# Qwiic_Pocket_Dev_ESP32_C6.net
KiCad netlist of a schematic drawn in EAGLE
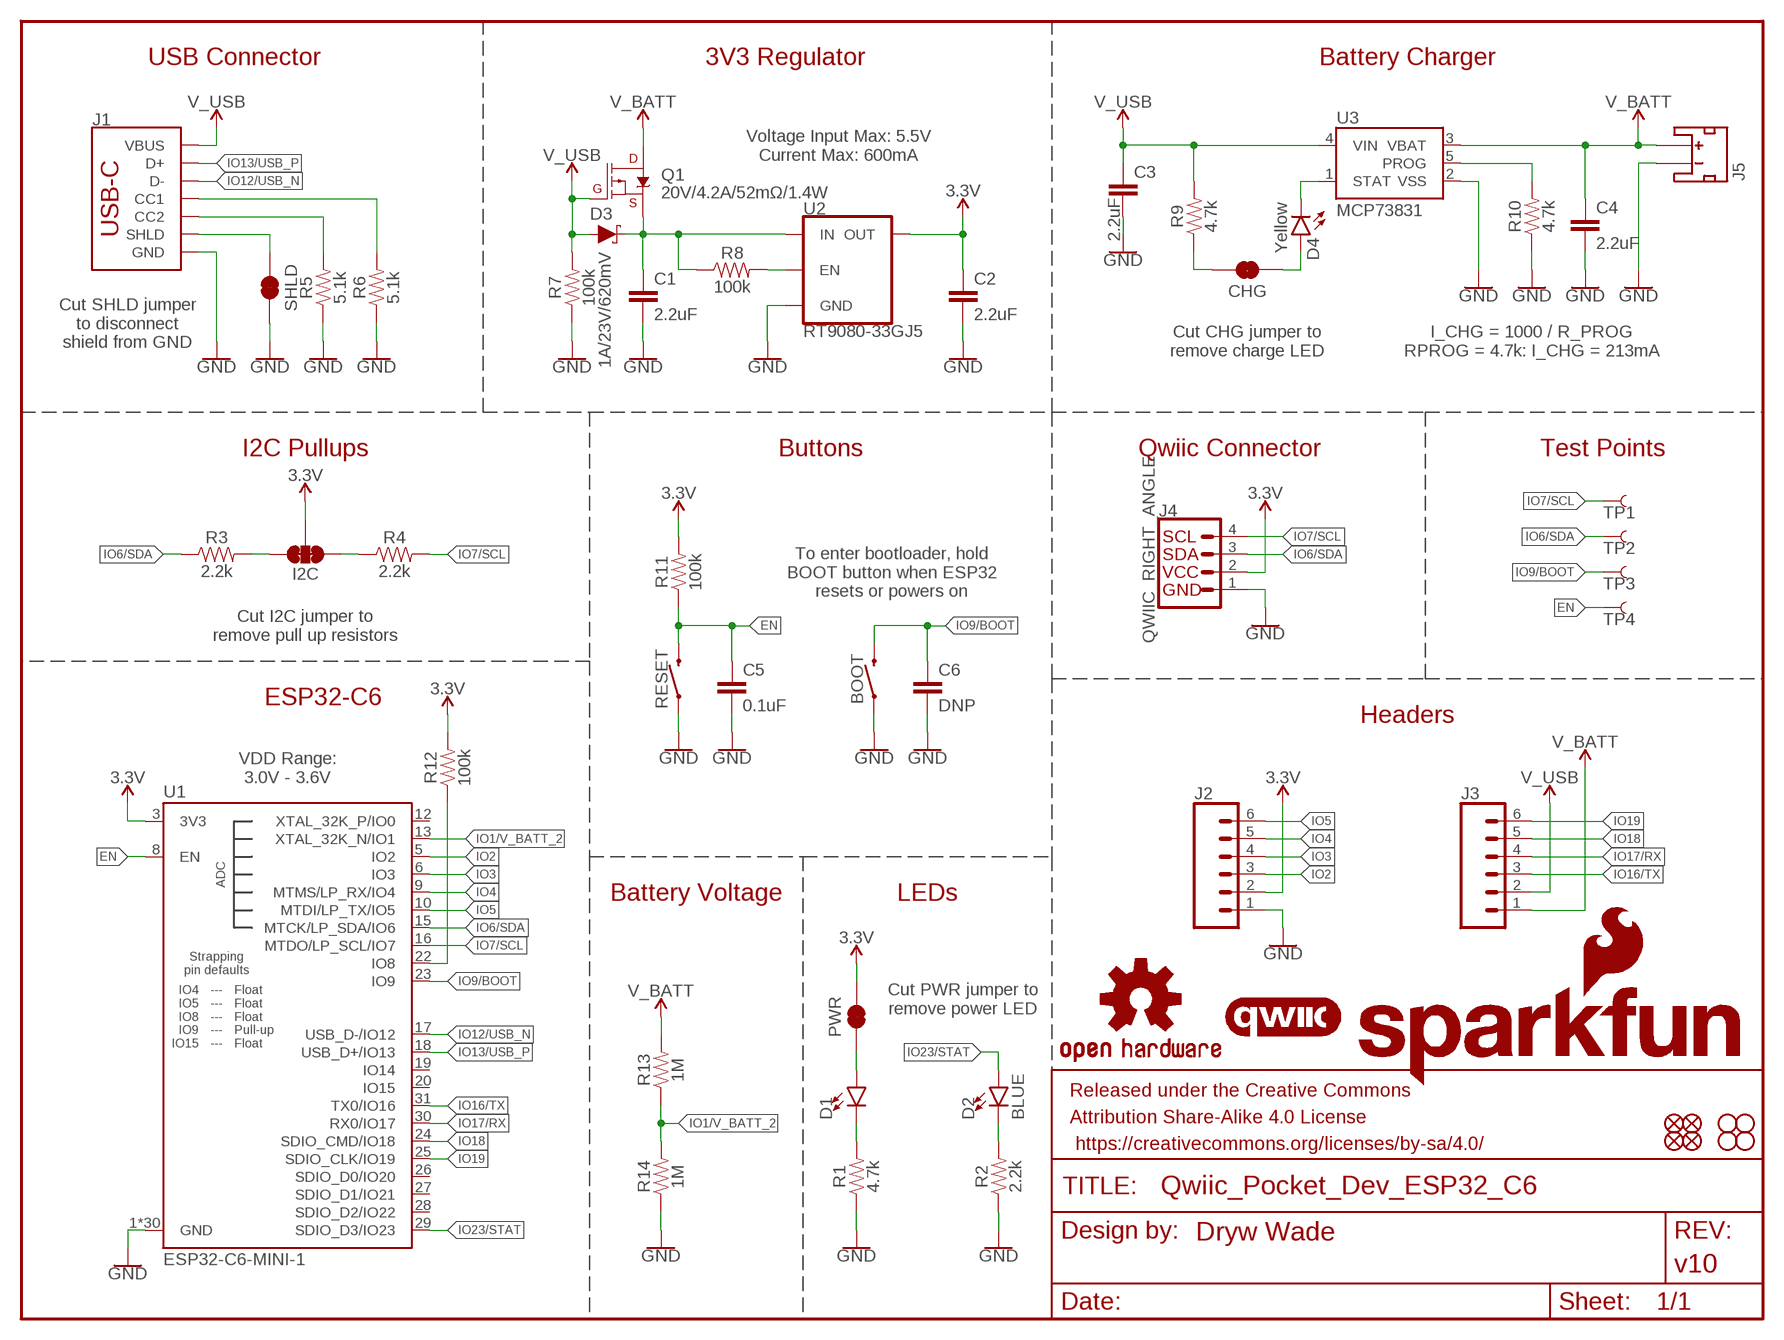
[diagram p0: schematic, sheet 1]

(export (version "E")
  (design (tool "Eeschema 10.0.6"))
  (components
    (comp (ref "BOOT")
      (value "MOMENTARY-SWITCH-SPST-SMD-4.6X2.8MM")
      (footprint "eagle-import:TACTILE_SWITCH_SMD_4.6X2.8MM")
      (libsource (lib "eagle-import") (part "MOMENTARY-SWITCH-SPST-SMD-4.6X2.8MM"))
    )
    (comp (ref "C1")
      (value "2.2uF")
      (footprint "eagle-import:0402-TIGHT")
      (libsource (lib "eagle-import") (part "2.2UF-0402_TIGHT-10V-10%-X5R"))
    )
    (comp (ref "C2")
      (value "2.2uF")
      (footprint "eagle-import:0402-TIGHT")
      (libsource (lib "eagle-import") (part "2.2UF-0402_TIGHT-10V-10%-X5R"))
    )
    (comp (ref "C3")
      (value "2.2uF")
      (footprint "eagle-import:0402-TIGHT")
      (libsource (lib "eagle-import") (part "2.2UF-0402_TIGHT-10V-10%-X5R"))
    )
    (comp (ref "C4")
      (value "2.2uF")
      (footprint "eagle-import:0402-TIGHT")
      (libsource (lib "eagle-import") (part "2.2UF-0402_TIGHT-10V-10%-X5R"))
    )
    (comp (ref "C5")
      (value "0.1uF")
      (footprint "eagle-import:0402-TIGHT")
      (libsource (lib "eagle-import") (part "0.1UF-0402T-6.3V-10%-X7R"))
    )
    (comp (ref "C6")
      (value "DNP")
      (footprint "eagle-import:0402-TIGHT")
      (libsource (lib "eagle-import") (part "0.1UF-0402T-6.3V-10%-X7R"))
    )
    (comp (ref "CHG")
      (value "JUMPER-SMT_2_NC_TRACE_SILK")
      (footprint "eagle-import:SMT-JUMPER_2_NC_TRACE_SILK")
      (libsource (lib "eagle-import") (part "JUMPER-SMT_2_NC_TRACE_SILK"))
    )
    (comp (ref "D1")
      (value "LED-RED_0603-KB")
      (footprint "eagle-import:LED-0603")
      (libsource (lib "eagle-import") (part "LED-RED_0603-KB"))
    )
    (comp (ref "D2")
      (value "BLUE")
      (footprint "eagle-import:LED-0603")
      (libsource (lib "eagle-import") (part "LED-BLUE0603"))
    )
    (comp (ref "D3")
      (value "1A/23V/620mV")
      (footprint "eagle-import:SOD-323")
      (libsource (lib "eagle-import") (part "DIODE-SCHOTTKY-BAT20J"))
    )
    (comp (ref "D4")
      (value "Yellow")
      (footprint "eagle-import:LED-0603")
      (libsource (lib "eagle-import") (part "LED-YELLOW0603"))
    )
    (comp (ref "FD1")
      (value "FIDUCIALUFIDUCIAL")
      (footprint "eagle-import:FIDUCIAL-MICRO")
      (libsource (lib "eagle-import") (part "FIDUCIALUFIDUCIAL"))
    )
    (comp (ref "FD2")
      (value "FIDUCIALUFIDUCIAL")
      (footprint "eagle-import:FIDUCIAL-MICRO")
      (libsource (lib "eagle-import") (part "FIDUCIALUFIDUCIAL"))
    )
    (comp (ref "FD3")
      (value "FIDUCIALUFIDUCIAL")
      (footprint "eagle-import:FIDUCIAL-MICRO")
      (libsource (lib "eagle-import") (part "FIDUCIALUFIDUCIAL"))
    )
    (comp (ref "FD4")
      (value "FIDUCIALUFIDUCIAL")
      (footprint "eagle-import:FIDUCIAL-MICRO")
      (libsource (lib "eagle-import") (part "FIDUCIALUFIDUCIAL"))
    )
    (comp (ref "FRAME1")
      (value "FRAME-LETTER")
      (footprint "eagle-import:CREATIVE_COMMONS")
      (fields (field (name "DESIGNER") "Dryw Wade") (field (name "REV") "v10"))
      (libsource (lib "eagle-import") (part "FRAME-LETTER"))
    )
    (comp (ref "H1")
      (value "STAND-OFF")
      (footprint "eagle-import:STAND-OFF")
      (libsource (lib "eagle-import") (part "STAND-OFF"))
    )
    (comp (ref "H2")
      (value "STAND-OFF")
      (footprint "eagle-import:STAND-OFF")
      (libsource (lib "eagle-import") (part "STAND-OFF"))
    )
    (comp (ref "H3")
      (value "STAND-OFF")
      (footprint "eagle-import:STAND-OFF")
      (libsource (lib "eagle-import") (part "STAND-OFF"))
    )
    (comp (ref "H4")
      (value "STAND-OFF")
      (footprint "eagle-import:STAND-OFF")
      (libsource (lib "eagle-import") (part "STAND-OFF"))
    )
    (comp (ref "I2C")
      (value "JUMPER-SMT_3_2-NC_TRACE_SILK")
      (footprint "eagle-import:SMT-JUMPER_3_2-NC_TRACE_SILK")
      (libsource (lib "eagle-import") (part "JUMPER-SMT_3_2-NC_TRACE_SILK"))
    )
    (comp (ref "J1")
      (value "USB Female Type C Connector")
      (footprint "eagle-import:USB-C-16P_4LAYER-PADS")
      (libsource (lib "eagle-import") (part "USB_C_4-LAYER_PADS"))
    )
    (comp (ref "J2")
      (value "CONN_06NO_SILK_NO_POP")
      (footprint "eagle-import:1X06_NO_SILK")
      (libsource (lib "eagle-import") (part "CONN_06NO_SILK_NO_POP"))
    )
    (comp (ref "J3")
      (value "CONN_06NO_SILK_NO_POP")
      (footprint "eagle-import:1X06_NO_SILK")
      (libsource (lib "eagle-import") (part "CONN_06NO_SILK_NO_POP"))
    )
    (comp (ref "J4")
      (value "QWIIC_RIGHT_ANGLE")
      (footprint "eagle-import:JST04_1MM_RA")
      (libsource (lib "eagle-import") (part "QWIIC_CONNECTORJS-1MM"))
    )
    (comp (ref "J5")
      (value "JST_2MM_MALE")
      (footprint "eagle-import:JST-2-SMD")
      (libsource (lib "eagle-import") (part "JST_2MM_MALE"))
    )
    (comp (ref "LOGO1")
      (value "SFE_LOGO_NAME_FLAMEBLANK")
      (footprint "eagle-import:BLANK")
      (libsource (lib "eagle-import") (part "SFE_LOGO_NAME_FLAMEBLANK"))
    )
    (comp (ref "LOGO2")
      (value "OSHW-LOGOS")
      (footprint "eagle-import:OSHW-LOGO-S")
      (libsource (lib "eagle-import") (part "OSHW-LOGOS"))
    )
    (comp (ref "LOGO3")
      (value "QWIIC_LOGO_3MM")
      (footprint "eagle-import:QWIIC_3MM")
      (libsource (lib "eagle-import") (part "QWIIC_LOGO_3MM"))
    )
    (comp (ref "PWR")
      (value "JUMPER-SMT_2_NC_TRACE_SILK")
      (footprint "eagle-import:SMT-JUMPER_2_NC_TRACE_SILK")
      (libsource (lib "eagle-import") (part "JUMPER-SMT_2_NC_TRACE_SILK"))
    )
    (comp (ref "Q1")
      (value "20V/4.2A/52mΩ/1.4W")
      (footprint "eagle-import:SOT23-3")
      (libsource (lib "eagle-import") (part "MOSFET_PCH-DMG2305UX-7"))
    )
    (comp (ref "R1")
      (value "4.7k")
      (footprint "eagle-import:0402-TIGHT")
      (libsource (lib "eagle-import") (part "4.7KOHM-0402T-1/16W-1%"))
    )
    (comp (ref "R2")
      (value "2.2k")
      (footprint "eagle-import:0402-TIGHT")
      (libsource (lib "eagle-import") (part "2.2KOHM-0402T-1/16W-1%"))
    )
    (comp (ref "R3")
      (value "2.2k")
      (footprint "eagle-import:0402-TIGHT")
      (libsource (lib "eagle-import") (part "2.2KOHM-0402T-1/16W-1%"))
    )
    (comp (ref "R4")
      (value "2.2k")
      (footprint "eagle-import:0402-TIGHT")
      (libsource (lib "eagle-import") (part "2.2KOHM-0402T-1/16W-1%"))
    )
    (comp (ref "R5")
      (value "5.1k")
      (footprint "eagle-import:0402-TIGHT")
      (libsource (lib "eagle-import") (part "5.1KOHM-0402T-1/16W-1%"))
    )
    (comp (ref "R6")
      (value "5.1k")
      (footprint "eagle-import:0402-TIGHT")
      (libsource (lib "eagle-import") (part "5.1KOHM-0402T-1/16W-1%"))
    )
    (comp (ref "R7")
      (value "100k")
      (footprint "eagle-import:0402-TIGHT")
      (libsource (lib "eagle-import") (part "100KOHM-0402T-1/16W-1%"))
    )
    (comp (ref "R8")
      (value "100k")
      (footprint "eagle-import:0402-TIGHT")
      (libsource (lib "eagle-import") (part "100KOHM-0402T-1/16W-1%"))
    )
    (comp (ref "R9")
      (value "4.7k")
      (footprint "eagle-import:0402-TIGHT")
      (libsource (lib "eagle-import") (part "4.7KOHM-0402T-1/16W-1%"))
    )
    (comp (ref "R10")
      (value "4.7k")
      (footprint "eagle-import:0402-TIGHT")
      (libsource (lib "eagle-import") (part "4.7KOHM-0402T-1/16W-1%"))
    )
    (comp (ref "R11")
      (value "100k")
      (footprint "eagle-import:0402-TIGHT")
      (libsource (lib "eagle-import") (part "100KOHM-0402T-1/16W-1%"))
    )
    (comp (ref "R12")
      (value "100k")
      (footprint "eagle-import:0402-TIGHT")
      (libsource (lib "eagle-import") (part "100KOHM-0402T-1/16W-1%"))
    )
    (comp (ref "R13")
      (value "1M")
      (footprint "eagle-import:0402-TIGHT")
      (libsource (lib "eagle-import") (part "1MOHM-0402T-1/16W-5%"))
    )
    (comp (ref "R14")
      (value "1M")
      (footprint "eagle-import:0402-TIGHT")
      (libsource (lib "eagle-import") (part "1MOHM-0402T-1/16W-5%"))
    )
    (comp (ref "RESET")
      (value "MOMENTARY-SWITCH-SPST-SMD-4.6X2.8MM")
      (footprint "eagle-import:TACTILE_SWITCH_SMD_4.6X2.8MM")
      (libsource (lib "eagle-import") (part "MOMENTARY-SWITCH-SPST-SMD-4.6X2.8MM"))
    )
    (comp (ref "SHLD")
      (value "JUMPER-SMT_2_NC_TRACE_SILK")
      (footprint "eagle-import:SMT-JUMPER_2_NC_TRACE_SILK")
      (libsource (lib "eagle-import") (part "JUMPER-SMT_2_NC_TRACE_SILK"))
    )
    (comp (ref "TP1")
      (value "TEST-POINT3")
      (footprint "eagle-import:PAD.03X.03")
      (libsource (lib "eagle-import") (part "TEST-POINT3"))
    )
    (comp (ref "TP2")
      (value "TEST-POINT3")
      (footprint "eagle-import:PAD.03X.03")
      (libsource (lib "eagle-import") (part "TEST-POINT3"))
    )
    (comp (ref "TP3")
      (value "TEST-POINT3")
      (footprint "eagle-import:PAD.03X.03")
      (libsource (lib "eagle-import") (part "TEST-POINT3"))
    )
    (comp (ref "TP4")
      (value "TEST-POINT3")
      (footprint "eagle-import:PAD.03X.03")
      (libsource (lib "eagle-import") (part "TEST-POINT3"))
    )
    (comp (ref "U1")
      (value "ESP32-C6-MINI-1")
      (footprint "eagle-import:ESP32-C6-MINI-1")
      (libsource (lib "eagle-import") (part "ESP32-C6-MINI-1"))
    )
    (comp (ref "U2")
      (value "RT9080-33GJ5")
      (footprint "eagle-import:SOT23-5")
      (libsource (lib "eagle-import") (part "V_REG_RT9080"))
    )
    (comp (ref "U3")
      (value "MCP73831")
      (footprint "eagle-import:SOT23-5")
      (libsource (lib "eagle-import") (part "MCP73831"))
    )
  )
  (nets
    (net (code "1") (name "3.3V") (class "Default")
      (node (ref "C2") (pin "1") (pinfunction "1_1") (pintype "passive"))
      (node (ref "I2C") (pin "2") (pinfunction "2_2") (pintype "passive"))
      (node (ref "J2") (pin "2") (pinfunction "2_2") (pintype "passive"))
      (node (ref "J4") (pin "2") (pinfunction "2_2") (pintype "power_in"))
      (node (ref "PWR") (pin "2") (pinfunction "2_2") (pintype "passive"))
      (node (ref "R11") (pin "2") (pinfunction "2_2") (pintype "passive"))
      (node (ref "R12") (pin "2") (pinfunction "2_2") (pintype "passive"))
      (node (ref "U1") (pin "3") (pinfunction "3V3_3") (pintype "bidirectional"))
      (node (ref "U2") (pin "5") (pinfunction "OUT_5") (pintype "passive"))
    )
    (net (code "2") (name "EN") (class "Default")
      (node (ref "C5") (pin "1") (pinfunction "1_1") (pintype "passive"))
      (node (ref "R11") (pin "1") (pinfunction "1_1") (pintype "passive"))
      (node (ref "RESET") (pin "3") (pinfunction "2_3") (pintype "passive"))
      (node (ref "RESET") (pin "4") (pinfunction "2_4") (pintype "passive"))
      (node (ref "TP4") (pin "1") (pinfunction "1_1") (pintype "bidirectional"))
      (node (ref "U1") (pin "8") (pinfunction "EN_8") (pintype "bidirectional"))
    )
    (net (code "3") (name "GND") (class "Default")
      (node (ref "BOOT") (pin "1") (pinfunction "1_1") (pintype "passive"))
      (node (ref "BOOT") (pin "2") (pinfunction "1_2") (pintype "passive"))
      (node (ref "C1") (pin "2") (pinfunction "2_2") (pintype "passive"))
      (node (ref "C2") (pin "2") (pinfunction "2_2") (pintype "passive"))
      (node (ref "C3") (pin "2") (pinfunction "2_2") (pintype "passive"))
      (node (ref "C4") (pin "2") (pinfunction "2_2") (pintype "passive"))
      (node (ref "C5") (pin "2") (pinfunction "2_2") (pintype "passive"))
      (node (ref "C6") (pin "2") (pinfunction "2_2") (pintype "passive"))
      (node (ref "J1") (pin "GND") (pinfunction "GND_GND") (pintype "bidirectional"))
      (node (ref "J1") (pin "GND2") (pinfunction "GND_GND2") (pintype "bidirectional"))
      (node (ref "J2") (pin "1") (pinfunction "1_1") (pintype "passive"))
      (node (ref "J4") (pin "1") (pinfunction "1_1") (pintype "power_in"))
      (node (ref "J5") (pin "1") (pinfunction "-_1") (pintype "bidirectional"))
      (node (ref "R1") (pin "1") (pinfunction "1_1") (pintype "passive"))
      (node (ref "R10") (pin "1") (pinfunction "1_1") (pintype "passive"))
      (node (ref "R14") (pin "1") (pinfunction "1_1") (pintype "passive"))
      (node (ref "R2") (pin "1") (pinfunction "1_1") (pintype "passive"))
      (node (ref "R5") (pin "1") (pinfunction "1_1") (pintype "passive"))
      (node (ref "R6") (pin "1") (pinfunction "1_1") (pintype "passive"))
      (node (ref "R7") (pin "1") (pinfunction "1_1") (pintype "passive"))
      (node (ref "RESET") (pin "1") (pinfunction "1_1") (pintype "passive"))
      (node (ref "RESET") (pin "2") (pinfunction "1_2") (pintype "passive"))
      (node (ref "SHLD") (pin "2") (pinfunction "2_2") (pintype "passive"))
      (node (ref "U1") (pin "1") (pinfunction "GND_1") (pintype "bidirectional"))
      (node (ref "U1") (pin "11") (pinfunction "GND_11") (pintype "bidirectional"))
      (node (ref "U1") (pin "14") (pinfunction "GND_14") (pintype "bidirectional"))
      (node (ref "U1") (pin "2") (pinfunction "GND_2") (pintype "bidirectional"))
      (node (ref "U1") (pin "36") (pinfunction "GND_36") (pintype "bidirectional"))
      (node (ref "U1") (pin "37") (pinfunction "GND_37") (pintype "bidirectional"))
      (node (ref "U1") (pin "38") (pinfunction "GND_38") (pintype "bidirectional"))
      (node (ref "U1") (pin "39") (pinfunction "GND_39") (pintype "bidirectional"))
      (node (ref "U1") (pin "40") (pinfunction "GND_40") (pintype "bidirectional"))
      (node (ref "U1") (pin "41") (pinfunction "GND_41") (pintype "bidirectional"))
      (node (ref "U1") (pin "42") (pinfunction "GND_42") (pintype "bidirectional"))
      (node (ref "U1") (pin "43") (pinfunction "GND_43") (pintype "bidirectional"))
      (node (ref "U1") (pin "44") (pinfunction "GND_44") (pintype "bidirectional"))
      (node (ref "U1") (pin "45") (pinfunction "GND_45") (pintype "bidirectional"))
      (node (ref "U1") (pin "46") (pinfunction "GND_46") (pintype "bidirectional"))
      (node (ref "U1") (pin "47") (pinfunction "GND_47") (pintype "bidirectional"))
      (node (ref "U1") (pin "48") (pinfunction "GND_48") (pintype "bidirectional"))
      (node (ref "U1") (pin "49.1") (pinfunction "GND_49.1") (pintype "bidirectional"))
      (node (ref "U1") (pin "49.2") (pinfunction "GND_49.2") (pintype "bidirectional"))
      (node (ref "U1") (pin "49.3") (pinfunction "GND_49.3") (pintype "bidirectional"))
      (node (ref "U1") (pin "49.4") (pinfunction "GND_49.4") (pintype "bidirectional"))
      (node (ref "U1") (pin "49.5") (pinfunction "GND_49.5") (pintype "bidirectional"))
      (node (ref "U1") (pin "49.6") (pinfunction "GND_49.6") (pintype "bidirectional"))
      (node (ref "U1") (pin "49.7") (pinfunction "GND_49.7") (pintype "bidirectional"))
      (node (ref "U1") (pin "49.8") (pinfunction "GND_49.8") (pintype "bidirectional"))
      (node (ref "U1") (pin "49.9") (pinfunction "GND_49.9") (pintype "bidirectional"))
      (node (ref "U1") (pin "50") (pinfunction "GND_50") (pintype "bidirectional"))
      (node (ref "U1") (pin "51") (pinfunction "GND_51") (pintype "bidirectional"))
      (node (ref "U1") (pin "52") (pinfunction "GND_52") (pintype "bidirectional"))
      (node (ref "U1") (pin "53") (pinfunction "GND_53") (pintype "bidirectional"))
      (node (ref "U2") (pin "2") (pinfunction "GND_2") (pintype "input"))
      (node (ref "U3") (pin "2") (pinfunction "VSS_2") (pintype "power_in"))
    )
    (net (code "4") (name "IO1{slash}V_BATT_2") (class "Default")
      (node (ref "R13") (pin "1") (pinfunction "1_1") (pintype "passive"))
      (node (ref "R14") (pin "2") (pinfunction "2_2") (pintype "passive"))
      (node (ref "U1") (pin "13") (pinfunction "XTAL_32K_N/IO1_13") (pintype "bidirectional"))
    )
    (net (code "5") (name "IO2") (class "Default")
      (node (ref "J2") (pin "3") (pinfunction "3_3") (pintype "passive"))
      (node (ref "U1") (pin "5") (pinfunction "IO2_5") (pintype "bidirectional"))
    )
    (net (code "6") (name "IO3") (class "Default")
      (node (ref "J2") (pin "4") (pinfunction "4_4") (pintype "passive"))
      (node (ref "U1") (pin "6") (pinfunction "IO3_6") (pintype "bidirectional"))
    )
    (net (code "7") (name "IO4") (class "Default")
      (node (ref "J2") (pin "5") (pinfunction "5_5") (pintype "passive"))
      (node (ref "U1") (pin "9") (pinfunction "MTMS/LP_RX/IO4_9") (pintype "bidirectional"))
    )
    (net (code "8") (name "IO5") (class "Default")
      (node (ref "J2") (pin "6") (pinfunction "6_6") (pintype "passive"))
      (node (ref "U1") (pin "10") (pinfunction "MTDI/LP_TX/IO5_10") (pintype "bidirectional"))
    )
    (net (code "9") (name "IO6{slash}SDA") (class "Default")
      (node (ref "J4") (pin "3") (pinfunction "3_3") (pintype "passive"))
      (node (ref "R3") (pin "1") (pinfunction "1_1") (pintype "passive"))
      (node (ref "TP2") (pin "1") (pinfunction "1_1") (pintype "bidirectional"))
      (node (ref "U1") (pin "15") (pinfunction "MTCK/LP_SDA/IO6_15") (pintype "bidirectional"))
    )
    (net (code "10") (name "IO7{slash}SCL") (class "Default")
      (node (ref "J4") (pin "4") (pinfunction "4_4") (pintype "passive"))
      (node (ref "R4") (pin "2") (pinfunction "2_2") (pintype "passive"))
      (node (ref "TP1") (pin "1") (pinfunction "1_1") (pintype "bidirectional"))
      (node (ref "U1") (pin "16") (pinfunction "MTDO/LP_SCL/IO7_16") (pintype "bidirectional"))
    )
    (net (code "11") (name "IO9{slash}BOOT") (class "Default")
      (node (ref "BOOT") (pin "3") (pinfunction "2_3") (pintype "passive"))
      (node (ref "BOOT") (pin "4") (pinfunction "2_4") (pintype "passive"))
      (node (ref "C6") (pin "1") (pinfunction "1_1") (pintype "passive"))
      (node (ref "TP3") (pin "1") (pinfunction "1_1") (pintype "bidirectional"))
      (node (ref "U1") (pin "23") (pinfunction "IO9_23") (pintype "bidirectional"))
    )
    (net (code "12") (name "IO12{slash}USB_N") (class "Default")
      (node (ref "J1") (pin "A7") (pinfunction "D-_A7") (pintype "bidirectional"))
      (node (ref "J1") (pin "B7") (pinfunction "D-_B7") (pintype "bidirectional"))
      (node (ref "U1") (pin "17") (pinfunction "USB_D-/IO12_17") (pintype "bidirectional"))
    )
    (net (code "13") (name "IO13{slash}USB_P") (class "Default")
      (node (ref "J1") (pin "A6") (pinfunction "D+_A6") (pintype "bidirectional"))
      (node (ref "J1") (pin "B6") (pinfunction "D+_B6") (pintype "bidirectional"))
      (node (ref "U1") (pin "18") (pinfunction "USB_D+/IO13_18") (pintype "bidirectional"))
    )
    (net (code "14") (name "IO16{slash}TX") (class "Default")
      (node (ref "J3") (pin "3") (pinfunction "3_3") (pintype "passive"))
      (node (ref "U1") (pin "31") (pinfunction "TX0/IO16_31") (pintype "bidirectional"))
    )
    (net (code "15") (name "IO17{slash}RX") (class "Default")
      (node (ref "J3") (pin "4") (pinfunction "4_4") (pintype "passive"))
      (node (ref "U1") (pin "30") (pinfunction "RX0/IO17_30") (pintype "bidirectional"))
    )
    (net (code "16") (name "IO18") (class "Default")
      (node (ref "J3") (pin "5") (pinfunction "5_5") (pintype "passive"))
      (node (ref "U1") (pin "24") (pinfunction "SDIO_CMD/IO18_24") (pintype "bidirectional"))
    )
    (net (code "17") (name "IO19") (class "Default")
      (node (ref "J3") (pin "6") (pinfunction "6_6") (pintype "passive"))
      (node (ref "U1") (pin "25") (pinfunction "SDIO_CLK/IO19_25") (pintype "bidirectional"))
    )
    (net (code "18") (name "IO23{slash}STAT") (class "Default")
      (node (ref "D2") (pin "A") (pinfunction "A_A") (pintype "passive"))
      (node (ref "U1") (pin "29") (pinfunction "SDIO_D3/IO23_29") (pintype "bidirectional"))
    )
    (net (code "19") (name "Net-(CHG-Pad1)") (class "Default")
      (node (ref "CHG") (pin "1") (pinfunction "1_1") (pintype "passive"))
      (node (ref "D4") (pin "A") (pinfunction "A_A") (pintype "passive"))
    )
    (net (code "20") (name "Net-(CHG-Pad2)") (class "Default")
      (node (ref "CHG") (pin "2") (pinfunction "2_2") (pintype "passive"))
      (node (ref "R9") (pin "1") (pinfunction "1_1") (pintype "passive"))
    )
    (net (code "21") (name "Net-(D1-PadA)") (class "Default")
      (node (ref "D1") (pin "A") (pinfunction "A_A") (pintype "passive"))
      (node (ref "PWR") (pin "1") (pinfunction "1_1") (pintype "passive"))
    )
    (net (code "22") (name "Net-(D1-PadC)") (class "Default")
      (node (ref "D1") (pin "C") (pinfunction "C_C") (pintype "passive"))
      (node (ref "R1") (pin "2") (pinfunction "2_2") (pintype "passive"))
    )
    (net (code "23") (name "Net-(D2-PadC)") (class "Default")
      (node (ref "D2") (pin "C") (pinfunction "C_C") (pintype "passive"))
      (node (ref "R2") (pin "2") (pinfunction "2_2") (pintype "passive"))
    )
    (net (code "24") (name "Net-(I2C-Pad1)") (class "Default")
      (node (ref "I2C") (pin "1") (pinfunction "1_1") (pintype "passive"))
      (node (ref "R4") (pin "1") (pinfunction "1_1") (pintype "passive"))
    )
    (net (code "25") (name "Net-(I2C-Pad3)") (class "Default")
      (node (ref "I2C") (pin "3") (pinfunction "3_3") (pintype "passive"))
      (node (ref "R3") (pin "2") (pinfunction "2_2") (pintype "passive"))
    )
    (net (code "26") (name "Net-(J1-CC1)") (class "Default")
      (node (ref "J1") (pin "A5") (pinfunction "CC1_A5") (pintype "bidirectional"))
      (node (ref "R6") (pin "2") (pinfunction "2_2") (pintype "passive"))
    )
    (net (code "27") (name "Net-(J1-CC2)") (class "Default")
      (node (ref "J1") (pin "B5") (pinfunction "CC2_B5") (pintype "bidirectional"))
      (node (ref "R5") (pin "2") (pinfunction "2_2") (pintype "passive"))
    )
    (net (code "28") (name "Net-(J1-SHLD-PadSHLD1)") (class "Default")
      (node (ref "J1") (pin "SHLD1") (pinfunction "SHLD_SHLD1") (pintype "bidirectional"))
      (node (ref "J1") (pin "SHLD2") (pinfunction "SHLD_SHLD2") (pintype "bidirectional"))
      (node (ref "J1") (pin "SHLD3") (pinfunction "SHLD_SHLD3") (pintype "bidirectional"))
      (node (ref "J1") (pin "SHLD4") (pinfunction "SHLD_SHLD4") (pintype "bidirectional"))
      (node (ref "SHLD") (pin "1") (pinfunction "1_1") (pintype "passive"))
    )
    (net (code "29") (name "Net-(Q1-S)") (class "Default")
      (node (ref "C1") (pin "1") (pinfunction "1_1") (pintype "passive"))
      (node (ref "D3") (pin "C") (pinfunction "C_C") (pintype "passive"))
      (node (ref "Q1") (pin "2") (pinfunction "S_2") (pintype "bidirectional"))
      (node (ref "R8") (pin "1") (pinfunction "1_1") (pintype "passive"))
      (node (ref "U2") (pin "1") (pinfunction "IN_1") (pintype "input"))
    )
    (net (code "30") (name "Net-(U1-IO8)") (class "Default")
      (node (ref "R12") (pin "1") (pinfunction "1_1") (pintype "passive"))
      (node (ref "U1") (pin "22") (pinfunction "IO8_22") (pintype "bidirectional"))
    )
    (net (code "31") (name "Net-(U2-EN)") (class "Default")
      (node (ref "R8") (pin "2") (pinfunction "2_2") (pintype "passive"))
      (node (ref "U2") (pin "3") (pinfunction "EN_3") (pintype "input"))
    )
    (net (code "32") (name "Net-(U3-PROG)") (class "Default")
      (node (ref "R10") (pin "2") (pinfunction "2_2") (pintype "passive"))
      (node (ref "U3") (pin "5") (pinfunction "PROG_5") (pintype "input"))
    )
    (net (code "33") (name "Net-(U3-STAT)") (class "Default")
      (node (ref "D4") (pin "C") (pinfunction "C_C") (pintype "passive"))
      (node (ref "U3") (pin "1") (pinfunction "STAT_1") (pintype "output"))
    )
    (net (code "34") (name "V_BATT") (class "Default")
      (node (ref "C4") (pin "1") (pinfunction "1_1") (pintype "passive"))
      (node (ref "J3") (pin "1") (pinfunction "1_1") (pintype "passive"))
      (node (ref "J5") (pin "2") (pinfunction "+_2") (pintype "bidirectional"))
      (node (ref "Q1") (pin "3") (pinfunction "D_3") (pintype "bidirectional"))
      (node (ref "R13") (pin "2") (pinfunction "2_2") (pintype "passive"))
      (node (ref "U3") (pin "3") (pinfunction "VBAT_3") (pintype "power_in"))
    )
    (net (code "35") (name "V_USB") (class "Default")
      (node (ref "C3") (pin "1") (pinfunction "1_1") (pintype "passive"))
      (node (ref "D3") (pin "A") (pinfunction "A_A") (pintype "passive"))
      (node (ref "J1") (pin "VBUS1") (pinfunction "VBUS_VBUS1") (pintype "bidirectional"))
      (node (ref "J1") (pin "VBUS2") (pinfunction "VBUS_VBUS2") (pintype "bidirectional"))
      (node (ref "J3") (pin "2") (pinfunction "2_2") (pintype "passive"))
      (node (ref "Q1") (pin "1") (pinfunction "G_1") (pintype "bidirectional"))
      (node (ref "R7") (pin "2") (pinfunction "2_2") (pintype "passive"))
      (node (ref "R9") (pin "2") (pinfunction "2_2") (pintype "passive"))
      (node (ref "U3") (pin "4") (pinfunction "VIN_4") (pintype "power_in"))
    )
    (net (code "36") (name "unconnected-(J5-PAD1-PadNC1)") (class "Default")
      (node (ref "J5") (pin "NC1") (pinfunction "PAD1_NC1") (pintype "bidirectional"))
    )
    (net (code "37") (name "unconnected-(J5-PAD2-PadNC2)") (class "Default")
      (node (ref "J5") (pin "NC2") (pinfunction "PAD2_NC2") (pintype "bidirectional"))
    )
    (net (code "38") (name "unconnected-(U1-IO14-Pad19)") (class "Default")
      (node (ref "U1") (pin "19") (pinfunction "IO14_19") (pintype "bidirectional"))
    )
    (net (code "39") (name "unconnected-(U1-IO15-Pad20)") (class "Default")
      (node (ref "U1") (pin "20") (pinfunction "IO15_20") (pintype "bidirectional"))
    )
    (net (code "40") (name "unconnected-(U1-SDIO_D0{slash}IO20-Pad26)") (class "Default")
      (node (ref "U1") (pin "26") (pinfunction "SDIO_D0/IO20_26") (pintype "bidirectional"))
    )
    (net (code "41") (name "unconnected-(U1-SDIO_D1{slash}IO21-Pad27)") (class "Default")
      (node (ref "U1") (pin "27") (pinfunction "SDIO_D1/IO21_27") (pintype "bidirectional"))
    )
    (net (code "42") (name "unconnected-(U1-SDIO_D2{slash}IO22-Pad28)") (class "Default")
      (node (ref "U1") (pin "28") (pinfunction "SDIO_D2/IO22_28") (pintype "bidirectional"))
    )
    (net (code "43") (name "unconnected-(U1-XTAL_32K_P{slash}IO0-Pad12)") (class "Default")
      (node (ref "U1") (pin "12") (pinfunction "XTAL_32K_P/IO0_12") (pintype "bidirectional"))
    )
  )
)
